# SAML21_Breakout.net
KiCad netlist of a schematic drawn in EAGLE
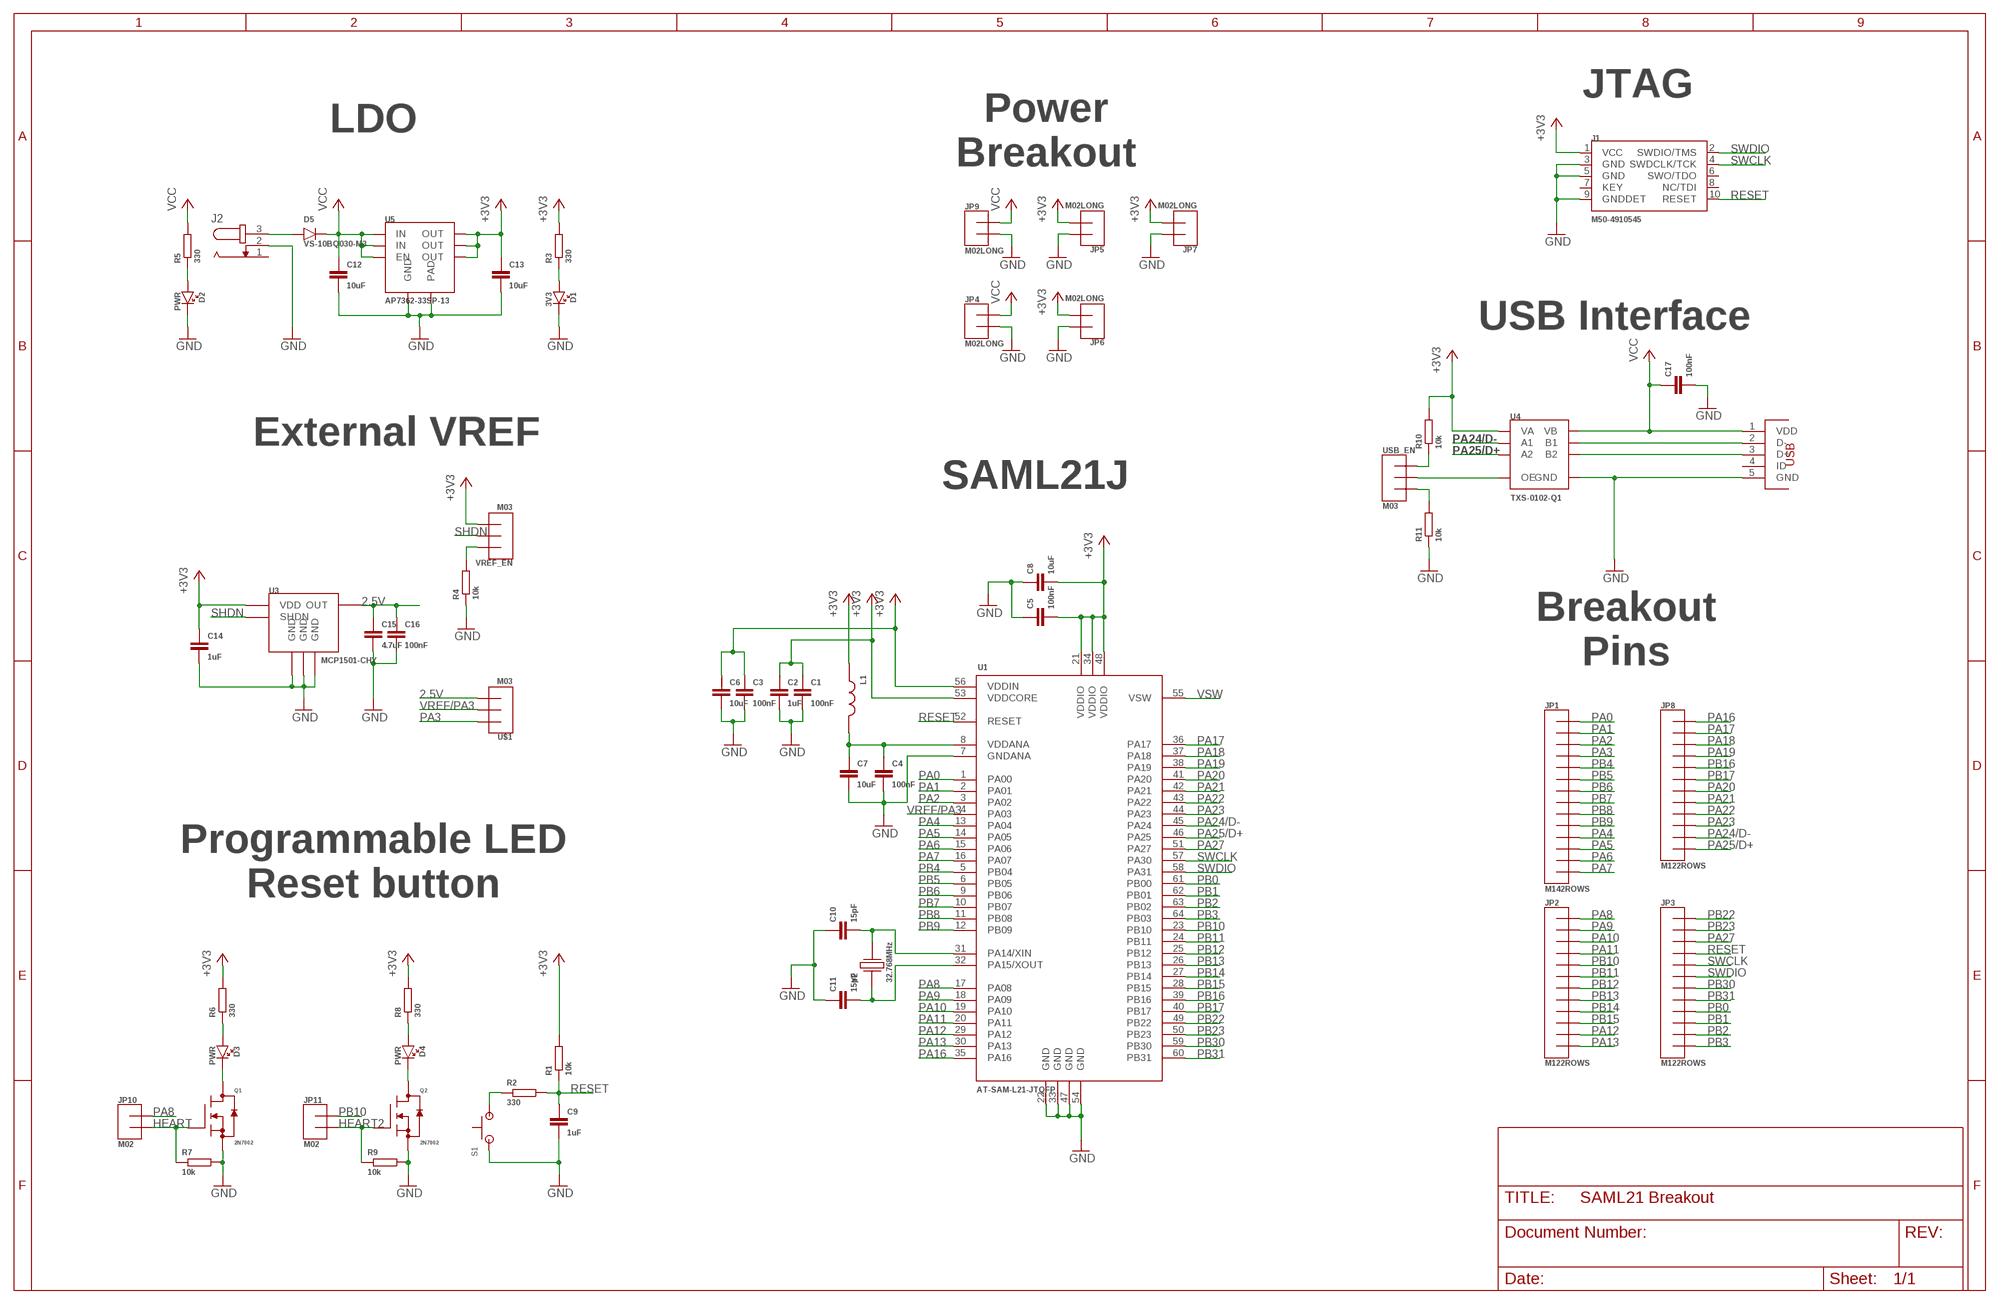
[diagram p0: schematic, sheet 1]

(export (version "E")
  (design (tool "Eeschema 10.0.6"))
  (components
    (comp (ref "C1")
      (value "100nF")
      (footprint "eagle-import:CAP-0603")
      (libsource (lib "eagle-import") (part "CAP0603"))
    )
    (comp (ref "C2")
      (value "1uF")
      (footprint "eagle-import:CAP-0603")
      (libsource (lib "eagle-import") (part "CAP0603"))
    )
    (comp (ref "C3")
      (value "100nF")
      (footprint "eagle-import:CAP-0603")
      (libsource (lib "eagle-import") (part "CAP0603"))
    )
    (comp (ref "C4")
      (value "100nF")
      (footprint "eagle-import:CAP-0603")
      (libsource (lib "eagle-import") (part "CAP0603"))
    )
    (comp (ref "C5")
      (value "100nF")
      (footprint "eagle-import:CAP-0603")
      (libsource (lib "eagle-import") (part "CAP0603"))
    )
    (comp (ref "C6")
      (value "10uF")
      (footprint "eagle-import:CAP-0603")
      (libsource (lib "eagle-import") (part "CAP0603"))
    )
    (comp (ref "C7")
      (value "10uF")
      (footprint "eagle-import:CAP-0603")
      (libsource (lib "eagle-import") (part "CAP0603"))
    )
    (comp (ref "C8")
      (value "10uF")
      (footprint "eagle-import:CAP-0603")
      (libsource (lib "eagle-import") (part "CAP0603"))
    )
    (comp (ref "C9")
      (value "1uF")
      (footprint "eagle-import:CAP-0603")
      (libsource (lib "eagle-import") (part "CAP0603"))
    )
    (comp (ref "C10")
      (value "15pF")
      (footprint "eagle-import:CAP-0603")
      (libsource (lib "eagle-import") (part "CAP0603"))
    )
    (comp (ref "C11")
      (value "15pF")
      (footprint "eagle-import:CAP-0603")
      (libsource (lib "eagle-import") (part "CAP0603"))
    )
    (comp (ref "C12")
      (value "10uF")
      (footprint "eagle-import:CAP-0603")
      (libsource (lib "eagle-import") (part "CAP0603"))
    )
    (comp (ref "C13")
      (value "10uF")
      (footprint "eagle-import:CAP-0603")
      (libsource (lib "eagle-import") (part "CAP0603"))
    )
    (comp (ref "C14")
      (value "1uF")
      (footprint "eagle-import:CAP-0603")
      (libsource (lib "eagle-import") (part "CAP0603"))
    )
    (comp (ref "C15")
      (value "4.7uF")
      (footprint "eagle-import:CAP-0603")
      (libsource (lib "eagle-import") (part "CAP0603"))
    )
    (comp (ref "C16")
      (value "100nF")
      (footprint "eagle-import:CAP-0603")
      (libsource (lib "eagle-import") (part "CAP0603"))
    )
    (comp (ref "C17")
      (value "100nF")
      (footprint "eagle-import:CAP-0603")
      (libsource (lib "eagle-import") (part "CAP0603"))
    )
    (comp (ref "D1")
      (value "3V3")
      (footprint "eagle-import:LED-1206")
      (libsource (lib "eagle-import") (part "LED1206"))
    )
    (comp (ref "D2")
      (value "PWR")
      (footprint "eagle-import:LED-1206")
      (libsource (lib "eagle-import") (part "LED1206"))
    )
    (comp (ref "D3")
      (value "PWR")
      (footprint "eagle-import:LED-1206")
      (libsource (lib "eagle-import") (part "LED1206"))
    )
    (comp (ref "D4")
      (value "PWR")
      (footprint "eagle-import:LED-1206")
      (libsource (lib "eagle-import") (part "LED1206"))
    )
    (comp (ref "D5")
      (value "VS-10BQ030-M3")
      (footprint "eagle-import:DO-214AA")
      (libsource (lib "eagle-import") (part "VS-10BQ030-M3"))
    )
    (comp (ref "J1")
      (value "M50-4910545")
      (footprint "eagle-import:M50-4910545")
      (libsource (lib "eagle-import") (part "M50-4910545"))
    )
    (comp (ref "J2")
      (value "JACK-PLUG0")
      (footprint "eagle-import:SPC4077")
      (libsource (lib "eagle-import") (part "JACK-PLUG0"))
    )
    (comp (ref "JP1")
      (value "M142ROWS")
      (footprint "eagle-import:2X07")
      (libsource (lib "eagle-import") (part "M142ROWS"))
    )
    (comp (ref "JP2")
      (value "M122ROWS")
      (footprint "eagle-import:2X06")
      (libsource (lib "eagle-import") (part "M122ROWS"))
    )
    (comp (ref "JP3")
      (value "M122ROWS")
      (footprint "eagle-import:2X06")
      (libsource (lib "eagle-import") (part "M122ROWS"))
    )
    (comp (ref "JP4")
      (value "M02LONG")
      (footprint "eagle-import:1X02-LONG")
      (libsource (lib "eagle-import") (part "M02LONG"))
    )
    (comp (ref "JP5")
      (value "M02LONG")
      (footprint "eagle-import:1X02-LONG")
      (libsource (lib "eagle-import") (part "M02LONG"))
    )
    (comp (ref "JP6")
      (value "M02LONG")
      (footprint "eagle-import:1X02-LONG")
      (libsource (lib "eagle-import") (part "M02LONG"))
    )
    (comp (ref "JP7")
      (value "M02LONG")
      (footprint "eagle-import:1X02-LONG")
      (libsource (lib "eagle-import") (part "M02LONG"))
    )
    (comp (ref "JP8")
      (value "M122ROWS")
      (footprint "eagle-import:2X06")
      (libsource (lib "eagle-import") (part "M122ROWS"))
    )
    (comp (ref "JP9")
      (value "M02LONG")
      (footprint "eagle-import:1X02-LONG")
      (libsource (lib "eagle-import") (part "M02LONG"))
    )
    (comp (ref "JP10")
      (value "M02")
      (footprint "eagle-import:1X02")
      (libsource (lib "eagle-import") (part "M02"))
    )
    (comp (ref "JP11")
      (value "M02")
      (footprint "eagle-import:1X02")
      (libsource (lib "eagle-import") (part "M02"))
    )
    (comp (ref "L1")
      (value "INDUCTOR0603")
      (footprint "eagle-import:IND-0603")
      (libsource (lib "eagle-import") (part "INDUCTOR0603"))
    )
    (comp (ref "Q1")
      (value "2N7002")
      (footprint "eagle-import:SOT-23-3")
      (libsource (lib "eagle-import") (part "2N7002"))
    )
    (comp (ref "Q2")
      (value "2N7002")
      (footprint "eagle-import:SOT-23-3")
      (libsource (lib "eagle-import") (part "2N7002"))
    )
    (comp (ref "R1")
      (value "10k")
      (footprint "eagle-import:RES-0805")
      (libsource (lib "eagle-import") (part "RESISTOR0805"))
    )
    (comp (ref "R2")
      (value "330")
      (footprint "eagle-import:RES-0805")
      (libsource (lib "eagle-import") (part "RESISTOR0805"))
    )
    (comp (ref "R3")
      (value "330")
      (footprint "eagle-import:RES-0805")
      (libsource (lib "eagle-import") (part "RESISTOR0805"))
    )
    (comp (ref "R4")
      (value "10k")
      (footprint "eagle-import:RES-0805")
      (libsource (lib "eagle-import") (part "RESISTOR0805"))
    )
    (comp (ref "R5")
      (value "330")
      (footprint "eagle-import:RES-0805")
      (libsource (lib "eagle-import") (part "RESISTOR0805"))
    )
    (comp (ref "R6")
      (value "330")
      (footprint "eagle-import:RES-0805")
      (libsource (lib "eagle-import") (part "RESISTOR0805"))
    )
    (comp (ref "R7")
      (value "10k")
      (footprint "eagle-import:RES-0805")
      (libsource (lib "eagle-import") (part "RESISTOR0805"))
    )
    (comp (ref "R8")
      (value "330")
      (footprint "eagle-import:RES-0805")
      (libsource (lib "eagle-import") (part "RESISTOR0805"))
    )
    (comp (ref "R9")
      (value "10k")
      (footprint "eagle-import:RES-0805")
      (libsource (lib "eagle-import") (part "RESISTOR0805"))
    )
    (comp (ref "R10")
      (value "10k")
      (footprint "eagle-import:RES-0805")
      (libsource (lib "eagle-import") (part "RESISTOR0805"))
    )
    (comp (ref "R11")
      (value "10k")
      (footprint "eagle-import:RES-0805")
      (libsource (lib "eagle-import") (part "RESISTOR0805"))
    )
    (comp (ref "S1")
      (value "SKHMQME010")
      (footprint "eagle-import:SKHMQME010")
      (libsource (lib "eagle-import") (part "SKHMQME010"))
    )
    (comp (ref "U$1")
      (value "M03")
      (footprint "eagle-import:1X03")
      (libsource (lib "eagle-import") (part "M03"))
    )
    (comp (ref "U$6")
      (value "MOLEX_USBMICRO")
      (footprint "eagle-import:MOLEX_47346-001")
      (libsource (lib "eagle-import") (part "MOLEX_USBMICRO"))
    )
    (comp (ref "U1")
      (value "AT-SAM-L21-JTQFP")
      (footprint "eagle-import:TQFP-64")
      (libsource (lib "eagle-import") (part "AT-SAM-L21-JTQFP"))
    )
    (comp (ref "U3")
      (value "MCP1501-CHY")
      (footprint "eagle-import:SOT-23-6")
      (libsource (lib "eagle-import") (part "MCP1501-CHY"))
    )
    (comp (ref "U4")
      (value "TXS-0102-Q1")
      (footprint "eagle-import:VSSOP-8")
      (libsource (lib "eagle-import") (part "TXS-0102-Q1"))
    )
    (comp (ref "U5")
      (value "AP7362-33SP-13")
      (footprint "eagle-import:SO-8EP")
      (libsource (lib "eagle-import") (part "AP7362-33SP-13"))
    )
    (comp (ref "USB_EN")
      (value "M03")
      (footprint "eagle-import:1X03")
      (libsource (lib "eagle-import") (part "M03"))
    )
    (comp (ref "VREF_EN")
      (value "M03")
      (footprint "eagle-import:1X03")
      (libsource (lib "eagle-import") (part "M03"))
    )
    (comp (ref "Y2")
      (value "32.768MHz")
      (footprint "eagle-import:CFPX-217")
      (libsource (lib "eagle-import") (part "LFXTAL054236-R"))
    )
  )
  (nets
    (net (code "1") (name "+3V3") (class "Default")
      (node (ref "C1") (pin "1") (pinfunction "1_1") (pintype "passive"))
      (node (ref "C13") (pin "1") (pinfunction "1_1") (pintype "passive"))
      (node (ref "C14") (pin "1") (pinfunction "1_1") (pintype "passive"))
      (node (ref "C2") (pin "1") (pinfunction "1_1") (pintype "passive"))
      (node (ref "C3") (pin "1") (pinfunction "1_1") (pintype "passive"))
      (node (ref "C5") (pin "2") (pinfunction "2_2") (pintype "passive"))
      (node (ref "C6") (pin "1") (pinfunction "1_1") (pintype "passive"))
      (node (ref "C8") (pin "2") (pinfunction "2_2") (pintype "passive"))
      (node (ref "J1") (pin "1") (pinfunction "VCC_1") (pintype "bidirectional"))
      (node (ref "JP5") (pin "2") (pinfunction "2_2") (pintype "bidirectional"))
      (node (ref "JP6") (pin "2") (pinfunction "2_2") (pintype "bidirectional"))
      (node (ref "JP7") (pin "2") (pinfunction "2_2") (pintype "bidirectional"))
      (node (ref "L1") (pin "1") (pinfunction "1_1") (pintype "passive"))
      (node (ref "R1") (pin "2") (pinfunction "2_2") (pintype "passive"))
      (node (ref "R10") (pin "2") (pinfunction "2_2") (pintype "passive"))
      (node (ref "R3") (pin "2") (pinfunction "2_2") (pintype "passive"))
      (node (ref "R6") (pin "2") (pinfunction "2_2") (pintype "passive"))
      (node (ref "R8") (pin "2") (pinfunction "2_2") (pintype "passive"))
      (node (ref "U1") (pin "21") (pinfunction "VDDIO_21") (pintype "power_in"))
      (node (ref "U1") (pin "34") (pinfunction "VDDIO_34") (pintype "power_in"))
      (node (ref "U1") (pin "48") (pinfunction "VDDIO_48") (pintype "power_in"))
      (node (ref "U1") (pin "53") (pinfunction "VDDCORE_53") (pintype "output"))
      (node (ref "U1") (pin "56") (pinfunction "VDDIN_56") (pintype "power_in"))
      (node (ref "U3") (pin "6") (pinfunction "VDD_6") (pintype "bidirectional"))
      (node (ref "U4") (pin "3") (pinfunction "VA_3") (pintype "bidirectional"))
      (node (ref "U5") (pin "5") (pinfunction "OUT_5") (pintype "bidirectional"))
      (node (ref "U5") (pin "6") (pinfunction "OUT_6") (pintype "bidirectional"))
      (node (ref "U5") (pin "7") (pinfunction "OUT_7") (pintype "bidirectional"))
      (node (ref "VREF_EN") (pin "3") (pinfunction "3_3") (pintype "bidirectional"))
    )
    (net (code "2") (name "/2.5V") (class "Default")
      (node (ref "C15") (pin "1") (pinfunction "1_1") (pintype "passive"))
      (node (ref "C16") (pin "1") (pinfunction "1_1") (pintype "passive"))
      (node (ref "U$1") (pin "3") (pinfunction "3_3") (pintype "bidirectional"))
      (node (ref "U3") (pin "1") (pinfunction "OUT_1") (pintype "bidirectional"))
    )
    (net (code "3") (name "/HEART") (class "Default")
      (node (ref "JP10") (pin "2") (pinfunction "2_2") (pintype "bidirectional"))
      (node (ref "Q1") (pin "D") (pinfunction "D_D") (pintype "bidirectional"))
      (node (ref "R7") (pin "1") (pinfunction "1_1") (pintype "passive"))
    )
    (net (code "4") (name "/HEART2") (class "Default")
      (node (ref "JP11") (pin "2") (pinfunction "2_2") (pintype "bidirectional"))
      (node (ref "Q2") (pin "D") (pinfunction "D_D") (pintype "bidirectional"))
      (node (ref "R9") (pin "1") (pinfunction "1_1") (pintype "passive"))
    )
    (net (code "5") (name "/PA0") (class "Default")
      (node (ref "JP1") (pin "1") (pinfunction "1_1") (pintype "bidirectional"))
      (node (ref "U1") (pin "1") (pinfunction "PA00_1") (pintype "bidirectional"))
    )
    (net (code "6") (name "/PA1") (class "Default")
      (node (ref "JP1") (pin "2") (pinfunction "2_2") (pintype "bidirectional"))
      (node (ref "U1") (pin "2") (pinfunction "PA01_2") (pintype "bidirectional"))
    )
    (net (code "7") (name "/PA2") (class "Default")
      (node (ref "JP1") (pin "3") (pinfunction "3_3") (pintype "bidirectional"))
      (node (ref "U1") (pin "3") (pinfunction "PA02_3") (pintype "bidirectional"))
    )
    (net (code "8") (name "/PA3") (class "Default")
      (node (ref "JP1") (pin "4") (pinfunction "4_4") (pintype "bidirectional"))
      (node (ref "U$1") (pin "1") (pinfunction "1_1") (pintype "bidirectional"))
    )
    (net (code "9") (name "/PA4") (class "Default")
      (node (ref "JP1") (pin "11") (pinfunction "11_11") (pintype "bidirectional"))
      (node (ref "U1") (pin "13") (pinfunction "PA04_13") (pintype "bidirectional"))
    )
    (net (code "10") (name "/PA5") (class "Default")
      (node (ref "JP1") (pin "12") (pinfunction "12_12") (pintype "bidirectional"))
      (node (ref "U1") (pin "14") (pinfunction "PA05_14") (pintype "bidirectional"))
    )
    (net (code "11") (name "/PA6") (class "Default")
      (node (ref "JP1") (pin "13") (pinfunction "13_13") (pintype "bidirectional"))
      (node (ref "U1") (pin "15") (pinfunction "PA06_15") (pintype "bidirectional"))
    )
    (net (code "12") (name "/PA7") (class "Default")
      (node (ref "JP1") (pin "14") (pinfunction "14_14") (pintype "bidirectional"))
      (node (ref "U1") (pin "16") (pinfunction "PA07_16") (pintype "bidirectional"))
    )
    (net (code "13") (name "/PA8") (class "Default")
      (node (ref "JP10") (pin "1") (pinfunction "1_1") (pintype "bidirectional"))
      (node (ref "JP2") (pin "1") (pinfunction "1_1") (pintype "bidirectional"))
      (node (ref "U1") (pin "17") (pinfunction "PA08_17") (pintype "bidirectional"))
    )
    (net (code "14") (name "/PA9") (class "Default")
      (node (ref "JP2") (pin "2") (pinfunction "2_2") (pintype "bidirectional"))
      (node (ref "U1") (pin "18") (pinfunction "PA09_18") (pintype "bidirectional"))
    )
    (net (code "15") (name "/PA10") (class "Default")
      (node (ref "JP2") (pin "3") (pinfunction "3_3") (pintype "bidirectional"))
      (node (ref "U1") (pin "19") (pinfunction "PA10_19") (pintype "bidirectional"))
    )
    (net (code "16") (name "/PA11") (class "Default")
      (node (ref "JP2") (pin "4") (pinfunction "4_4") (pintype "bidirectional"))
      (node (ref "U1") (pin "20") (pinfunction "PA11_20") (pintype "bidirectional"))
    )
    (net (code "17") (name "/PA12") (class "Default")
      (node (ref "JP2") (pin "11") (pinfunction "11_11") (pintype "bidirectional"))
      (node (ref "U1") (pin "29") (pinfunction "PA12_29") (pintype "bidirectional"))
    )
    (net (code "18") (name "/PA13") (class "Default")
      (node (ref "JP2") (pin "12") (pinfunction "12_12") (pintype "bidirectional"))
      (node (ref "U1") (pin "30") (pinfunction "PA13_30") (pintype "bidirectional"))
    )
    (net (code "19") (name "/PA16") (class "Default")
      (node (ref "JP8") (pin "1") (pinfunction "1_1") (pintype "bidirectional"))
      (node (ref "U1") (pin "35") (pinfunction "PA16_35") (pintype "bidirectional"))
    )
    (net (code "20") (name "/PA17") (class "Default")
      (node (ref "JP8") (pin "2") (pinfunction "2_2") (pintype "bidirectional"))
      (node (ref "U1") (pin "36") (pinfunction "PA17_36") (pintype "bidirectional"))
    )
    (net (code "21") (name "/PA18") (class "Default")
      (node (ref "JP8") (pin "3") (pinfunction "3_3") (pintype "bidirectional"))
      (node (ref "U1") (pin "37") (pinfunction "PA18_37") (pintype "bidirectional"))
    )
    (net (code "22") (name "/PA19") (class "Default")
      (node (ref "JP8") (pin "4") (pinfunction "4_4") (pintype "bidirectional"))
      (node (ref "U1") (pin "38") (pinfunction "PA19_38") (pintype "bidirectional"))
    )
    (net (code "23") (name "/PA20") (class "Default")
      (node (ref "JP8") (pin "7") (pinfunction "7_7") (pintype "bidirectional"))
      (node (ref "U1") (pin "41") (pinfunction "PA20_41") (pintype "bidirectional"))
    )
    (net (code "24") (name "/PA21") (class "Default")
      (node (ref "JP8") (pin "8") (pinfunction "8_8") (pintype "bidirectional"))
      (node (ref "U1") (pin "42") (pinfunction "PA21_42") (pintype "bidirectional"))
    )
    (net (code "25") (name "/PA22") (class "Default")
      (node (ref "JP8") (pin "9") (pinfunction "9_9") (pintype "bidirectional"))
      (node (ref "U1") (pin "43") (pinfunction "PA22_43") (pintype "bidirectional"))
    )
    (net (code "26") (name "/PA23") (class "Default")
      (node (ref "JP8") (pin "10") (pinfunction "10_10") (pintype "bidirectional"))
      (node (ref "U1") (pin "44") (pinfunction "PA23_44") (pintype "bidirectional"))
    )
    (net (code "27") (name "/PA24{slash}D-") (class "Default")
      (node (ref "JP8") (pin "11") (pinfunction "11_11") (pintype "bidirectional"))
      (node (ref "U1") (pin "45") (pinfunction "PA24_45") (pintype "bidirectional"))
      (node (ref "U4") (pin "5") (pinfunction "A1_5") (pintype "bidirectional"))
    )
    (net (code "28") (name "/PA25{slash}D+") (class "Default")
      (node (ref "JP8") (pin "12") (pinfunction "12_12") (pintype "bidirectional"))
      (node (ref "U1") (pin "46") (pinfunction "PA25_46") (pintype "bidirectional"))
      (node (ref "U4") (pin "4") (pinfunction "A2_4") (pintype "bidirectional"))
    )
    (net (code "29") (name "/PA27") (class "Default")
      (node (ref "JP3") (pin "3") (pinfunction "3_3") (pintype "bidirectional"))
      (node (ref "U1") (pin "51") (pinfunction "PA27_51") (pintype "bidirectional"))
    )
    (net (code "30") (name "/PB0") (class "Default")
      (node (ref "JP3") (pin "9") (pinfunction "9_9") (pintype "bidirectional"))
      (node (ref "U1") (pin "61") (pinfunction "PB00_61") (pintype "bidirectional"))
    )
    (net (code "31") (name "/PB1") (class "Default")
      (node (ref "JP3") (pin "10") (pinfunction "10_10") (pintype "bidirectional"))
      (node (ref "U1") (pin "62") (pinfunction "PB01_62") (pintype "bidirectional"))
    )
    (net (code "32") (name "/PB2") (class "Default")
      (node (ref "JP3") (pin "11") (pinfunction "11_11") (pintype "bidirectional"))
      (node (ref "U1") (pin "63") (pinfunction "PB02_63") (pintype "bidirectional"))
    )
    (net (code "33") (name "/PB3") (class "Default")
      (node (ref "JP3") (pin "12") (pinfunction "12_12") (pintype "bidirectional"))
      (node (ref "U1") (pin "64") (pinfunction "PB03_64") (pintype "bidirectional"))
    )
    (net (code "34") (name "/PB4") (class "Default")
      (node (ref "JP1") (pin "5") (pinfunction "5_5") (pintype "bidirectional"))
      (node (ref "U1") (pin "5") (pinfunction "PB04_5") (pintype "bidirectional"))
    )
    (net (code "35") (name "/PB5") (class "Default")
      (node (ref "JP1") (pin "6") (pinfunction "6_6") (pintype "bidirectional"))
      (node (ref "U1") (pin "6") (pinfunction "PB05_6") (pintype "bidirectional"))
    )
    (net (code "36") (name "/PB6") (class "Default")
      (node (ref "JP1") (pin "7") (pinfunction "7_7") (pintype "bidirectional"))
      (node (ref "U1") (pin "9") (pinfunction "PB06_9") (pintype "bidirectional"))
    )
    (net (code "37") (name "/PB7") (class "Default")
      (node (ref "JP1") (pin "8") (pinfunction "8_8") (pintype "bidirectional"))
      (node (ref "U1") (pin "10") (pinfunction "PB07_10") (pintype "bidirectional"))
    )
    (net (code "38") (name "/PB8") (class "Default")
      (node (ref "JP1") (pin "9") (pinfunction "9_9") (pintype "bidirectional"))
      (node (ref "U1") (pin "11") (pinfunction "PB08_11") (pintype "bidirectional"))
    )
    (net (code "39") (name "/PB9") (class "Default")
      (node (ref "JP1") (pin "10") (pinfunction "10_10") (pintype "bidirectional"))
      (node (ref "U1") (pin "12") (pinfunction "PB09_12") (pintype "bidirectional"))
    )
    (net (code "40") (name "/PB10") (class "Default")
      (node (ref "JP11") (pin "1") (pinfunction "1_1") (pintype "bidirectional"))
      (node (ref "JP2") (pin "5") (pinfunction "5_5") (pintype "bidirectional"))
      (node (ref "U1") (pin "23") (pinfunction "PB10_23") (pintype "bidirectional"))
    )
    (net (code "41") (name "/PB11") (class "Default")
      (node (ref "JP2") (pin "6") (pinfunction "6_6") (pintype "bidirectional"))
      (node (ref "U1") (pin "24") (pinfunction "PB11_24") (pintype "bidirectional"))
    )
    (net (code "42") (name "/PB12") (class "Default")
      (node (ref "JP2") (pin "7") (pinfunction "7_7") (pintype "bidirectional"))
      (node (ref "U1") (pin "25") (pinfunction "PB12_25") (pintype "bidirectional"))
    )
    (net (code "43") (name "/PB13") (class "Default")
      (node (ref "JP2") (pin "8") (pinfunction "8_8") (pintype "bidirectional"))
      (node (ref "U1") (pin "26") (pinfunction "PB13_26") (pintype "bidirectional"))
    )
    (net (code "44") (name "/PB14") (class "Default")
      (node (ref "JP2") (pin "9") (pinfunction "9_9") (pintype "bidirectional"))
      (node (ref "U1") (pin "27") (pinfunction "PB14_27") (pintype "bidirectional"))
    )
    (net (code "45") (name "/PB15") (class "Default")
      (node (ref "JP2") (pin "10") (pinfunction "10_10") (pintype "bidirectional"))
      (node (ref "U1") (pin "28") (pinfunction "PB15_28") (pintype "bidirectional"))
    )
    (net (code "46") (name "/PB16") (class "Default")
      (node (ref "JP8") (pin "5") (pinfunction "5_5") (pintype "bidirectional"))
      (node (ref "U1") (pin "39") (pinfunction "PB16_39") (pintype "bidirectional"))
    )
    (net (code "47") (name "/PB17") (class "Default")
      (node (ref "JP8") (pin "6") (pinfunction "6_6") (pintype "bidirectional"))
      (node (ref "U1") (pin "40") (pinfunction "PB17_40") (pintype "bidirectional"))
    )
    (net (code "48") (name "/PB22") (class "Default")
      (node (ref "JP3") (pin "1") (pinfunction "1_1") (pintype "bidirectional"))
      (node (ref "U1") (pin "49") (pinfunction "PB22_49") (pintype "bidirectional"))
    )
    (net (code "49") (name "/PB23") (class "Default")
      (node (ref "JP3") (pin "2") (pinfunction "2_2") (pintype "bidirectional"))
      (node (ref "U1") (pin "50") (pinfunction "PB23_50") (pintype "bidirectional"))
    )
    (net (code "50") (name "/PB30") (class "Default")
      (node (ref "JP3") (pin "7") (pinfunction "7_7") (pintype "bidirectional"))
      (node (ref "U1") (pin "59") (pinfunction "PB30_59") (pintype "bidirectional"))
    )
    (net (code "51") (name "/PB31") (class "Default")
      (node (ref "JP3") (pin "8") (pinfunction "8_8") (pintype "bidirectional"))
      (node (ref "U1") (pin "60") (pinfunction "PB31_60") (pintype "bidirectional"))
    )
    (net (code "52") (name "/RESET") (class "Default")
      (node (ref "C9") (pin "1") (pinfunction "1_1") (pintype "passive"))
      (node (ref "J1") (pin "10") (pinfunction "RESET_10") (pintype "bidirectional"))
      (node (ref "JP3") (pin "4") (pinfunction "4_4") (pintype "bidirectional"))
      (node (ref "R1") (pin "1") (pinfunction "1_1") (pintype "passive"))
      (node (ref "R2") (pin "2") (pinfunction "2_2") (pintype "passive"))
      (node (ref "U1") (pin "52") (pinfunction "RESET_52") (pintype "bidirectional"))
    )
    (net (code "53") (name "/SHDN") (class "Default")
      (node (ref "U3") (pin "4") (pinfunction "SHDN_4") (pintype "bidirectional"))
      (node (ref "VREF_EN") (pin "2") (pinfunction "2_2") (pintype "bidirectional"))
    )
    (net (code "54") (name "/SWCLK") (class "Default")
      (node (ref "J1") (pin "4") (pinfunction "SWDCLK/TCK_4") (pintype "bidirectional"))
      (node (ref "JP3") (pin "5") (pinfunction "5_5") (pintype "bidirectional"))
      (node (ref "U1") (pin "57") (pinfunction "PA30_57") (pintype "bidirectional"))
    )
    (net (code "55") (name "/SWDIO") (class "Default")
      (node (ref "J1") (pin "2") (pinfunction "SWDIO/TMS_2") (pintype "bidirectional"))
      (node (ref "JP3") (pin "6") (pinfunction "6_6") (pintype "bidirectional"))
      (node (ref "U1") (pin "58") (pinfunction "PA31_58") (pintype "bidirectional"))
    )
    (net (code "56") (name "/VREF{slash}PA3") (class "Default")
      (node (ref "U$1") (pin "2") (pinfunction "2_2") (pintype "bidirectional"))
      (node (ref "U1") (pin "4") (pinfunction "PA03_4") (pintype "bidirectional"))
    )
    (net (code "57") (name "/VSW") (class "Default")
      (node (ref "U1") (pin "55") (pinfunction "VSW_55") (pintype "bidirectional"))
    )
    (net (code "58") (name "GND") (class "Default")
      (node (ref "C1") (pin "2") (pinfunction "2_2") (pintype "passive"))
      (node (ref "C10") (pin "1") (pinfunction "1_1") (pintype "passive"))
      (node (ref "C11") (pin "1") (pinfunction "1_1") (pintype "passive"))
      (node (ref "C12") (pin "2") (pinfunction "2_2") (pintype "passive"))
      (node (ref "C13") (pin "2") (pinfunction "2_2") (pintype "passive"))
      (node (ref "C14") (pin "2") (pinfunction "2_2") (pintype "passive"))
      (node (ref "C15") (pin "2") (pinfunction "2_2") (pintype "passive"))
      (node (ref "C16") (pin "2") (pinfunction "2_2") (pintype "passive"))
      (node (ref "C17") (pin "2") (pinfunction "2_2") (pintype "passive"))
      (node (ref "C2") (pin "2") (pinfunction "2_2") (pintype "passive"))
      (node (ref "C3") (pin "2") (pinfunction "2_2") (pintype "passive"))
      (node (ref "C4") (pin "2") (pinfunction "2_2") (pintype "passive"))
      (node (ref "C5") (pin "1") (pinfunction "1_1") (pintype "passive"))
      (node (ref "C6") (pin "2") (pinfunction "2_2") (pintype "passive"))
      (node (ref "C7") (pin "2") (pinfunction "2_2") (pintype "passive"))
      (node (ref "C8") (pin "1") (pinfunction "1_1") (pintype "passive"))
      (node (ref "C9") (pin "2") (pinfunction "2_2") (pintype "passive"))
      (node (ref "D1") (pin "C") (pinfunction "C_C") (pintype "bidirectional"))
      (node (ref "D2") (pin "C") (pinfunction "C_C") (pintype "bidirectional"))
      (node (ref "J1") (pin "3") (pinfunction "GND_3") (pintype "bidirectional"))
      (node (ref "J1") (pin "5") (pinfunction "GND_5") (pintype "bidirectional"))
      (node (ref "J1") (pin "9") (pinfunction "GNDDET_9") (pintype "bidirectional"))
      (node (ref "J2") (pin "2") (pinfunction "2_2") (pintype "passive"))
      (node (ref "JP4") (pin "2") (pinfunction "2_2") (pintype "bidirectional"))
      (node (ref "JP5") (pin "1") (pinfunction "1_1") (pintype "bidirectional"))
      (node (ref "JP6") (pin "1") (pinfunction "1_1") (pintype "bidirectional"))
      (node (ref "JP7") (pin "1") (pinfunction "1_1") (pintype "bidirectional"))
      (node (ref "JP9") (pin "2") (pinfunction "2_2") (pintype "bidirectional"))
      (node (ref "Q1") (pin "S") (pinfunction "S_S") (pintype "bidirectional"))
      (node (ref "Q2") (pin "S") (pinfunction "S_S") (pintype "bidirectional"))
      (node (ref "R11") (pin "1") (pinfunction "1_1") (pintype "passive"))
      (node (ref "R4") (pin "1") (pinfunction "1_1") (pintype "passive"))
      (node (ref "R7") (pin "2") (pinfunction "2_2") (pintype "passive"))
      (node (ref "R9") (pin "2") (pinfunction "2_2") (pintype "passive"))
      (node (ref "S1") (pin "1") (pinfunction "1_1") (pintype "bidirectional"))
      (node (ref "U$6") (pin "5") (pinfunction "GND_5") (pintype "bidirectional"))
      (node (ref "U1") (pin "22") (pinfunction "GND_22") (pintype "power_in"))
      (node (ref "U1") (pin "33") (pinfunction "GND_33") (pintype "power_in"))
      (node (ref "U1") (pin "47") (pinfunction "GND_47") (pintype "power_in"))
      (node (ref "U1") (pin "54") (pinfunction "GND_54") (pintype "power_in"))
      (node (ref "U1") (pin "7") (pinfunction "GNDANA_7") (pintype "power_in"))
      (node (ref "U3") (pin "2") (pinfunction "GND_2") (pintype "bidirectional"))
      (node (ref "U3") (pin "3") (pinfunction "GND_3") (pintype "bidirectional"))
      (node (ref "U3") (pin "5") (pinfunction "GND_5") (pintype "bidirectional"))
      (node (ref "U4") (pin "2") (pinfunction "GND_2") (pintype "bidirectional"))
      (node (ref "U5") (pin "1") (pinfunction "GND_1") (pintype "bidirectional"))
      (node (ref "U5") (pin "PAD") (pinfunction "PAD_PAD") (pintype "bidirectional"))
    )
    (net (code "59") (name "Net-(D1-PadA)") (class "Default")
      (node (ref "D1") (pin "A") (pinfunction "A_A") (pintype "bidirectional"))
      (node (ref "R3") (pin "1") (pinfunction "1_1") (pintype "passive"))
    )
    (net (code "60") (name "Net-(D2-PadA)") (class "Default")
      (node (ref "D2") (pin "A") (pinfunction "A_A") (pintype "bidirectional"))
      (node (ref "R5") (pin "1") (pinfunction "1_1") (pintype "passive"))
    )
    (net (code "61") (name "Net-(D3-PadA)") (class "Default")
      (node (ref "D3") (pin "A") (pinfunction "A_A") (pintype "bidirectional"))
      (node (ref "R6") (pin "1") (pinfunction "1_1") (pintype "passive"))
    )
    (net (code "62") (name "Net-(D3-PadC)") (class "Default")
      (node (ref "D3") (pin "C") (pinfunction "C_C") (pintype "bidirectional"))
      (node (ref "Q1") (pin "G") (pinfunction "G_G") (pintype "bidirectional"))
    )
    (net (code "63") (name "Net-(D4-PadA)") (class "Default")
      (node (ref "D4") (pin "A") (pinfunction "A_A") (pintype "bidirectional"))
      (node (ref "R8") (pin "1") (pinfunction "1_1") (pintype "passive"))
    )
    (net (code "64") (name "Net-(D4-PadC)") (class "Default")
      (node (ref "D4") (pin "C") (pinfunction "C_C") (pintype "bidirectional"))
      (node (ref "Q2") (pin "G") (pinfunction "G_G") (pintype "bidirectional"))
    )
    (net (code "65") (name "Net-(D5-PadA)") (class "Default")
      (node (ref "D5") (pin "A") (pinfunction "A_A") (pintype "bidirectional"))
      (node (ref "J2") (pin "3") (pinfunction "3_3") (pintype "passive"))
    )
    (net (code "66") (name "Net-(R4-Pad2)") (class "Default")
      (node (ref "R4") (pin "2") (pinfunction "2_2") (pintype "passive"))
      (node (ref "VREF_EN") (pin "1") (pinfunction "1_1") (pintype "bidirectional"))
    )
    (net (code "67") (name "Net-(R10-Pad1)") (class "Default")
      (node (ref "R10") (pin "1") (pinfunction "1_1") (pintype "passive"))
      (node (ref "USB_EN") (pin "1") (pinfunction "1_1") (pintype "bidirectional"))
    )
    (net (code "68") (name "Net-(R11-Pad2)") (class "Default")
      (node (ref "R11") (pin "2") (pinfunction "2_2") (pintype "passive"))
      (node (ref "USB_EN") (pin "3") (pinfunction "3_3") (pintype "bidirectional"))
    )
    (net (code "69") (name "Net-(S1-2)") (class "Default")
      (node (ref "R2") (pin "1") (pinfunction "1_1") (pintype "passive"))
      (node (ref "S1") (pin "3") (pinfunction "2_3") (pintype "bidirectional"))
    )
    (net (code "70") (name "Net-(U$6-D+)") (class "Default")
      (node (ref "U$6") (pin "3") (pinfunction "D+_3") (pintype "bidirectional"))
      (node (ref "U4") (pin "1") (pinfunction "B2_1") (pintype "bidirectional"))
    )
    (net (code "71") (name "Net-(U$6-D-)") (class "Default")
      (node (ref "U$6") (pin "2") (pinfunction "D-_2") (pintype "bidirectional"))
      (node (ref "U4") (pin "8") (pinfunction "B1_8") (pintype "bidirectional"))
    )
    (net (code "72") (name "Net-(U1-PA14{slash}XIN)") (class "Default")
      (node (ref "C10") (pin "2") (pinfunction "2_2") (pintype "passive"))
      (node (ref "U1") (pin "31") (pinfunction "PA14/XIN_31") (pintype "bidirectional"))
      (node (ref "Y2") (pin "2") (pinfunction "2_2") (pintype "bidirectional"))
    )
    (net (code "73") (name "Net-(U1-PA15{slash}XOUT)") (class "Default")
      (node (ref "C11") (pin "2") (pinfunction "2_2") (pintype "passive"))
      (node (ref "U1") (pin "32") (pinfunction "PA15/XOUT_32") (pintype "bidirectional"))
      (node (ref "Y2") (pin "1") (pinfunction "1_1") (pintype "bidirectional"))
    )
    (net (code "74") (name "Net-(U1-VDDANA)") (class "Default")
      (node (ref "C4") (pin "1") (pinfunction "1_1") (pintype "passive"))
      (node (ref "C7") (pin "1") (pinfunction "1_1") (pintype "passive"))
      (node (ref "L1") (pin "2") (pinfunction "2_2") (pintype "passive"))
      (node (ref "U1") (pin "8") (pinfunction "VDDANA_8") (pintype "power_in"))
    )
    (net (code "75") (name "Net-(U4-OE)") (class "Default")
      (node (ref "U4") (pin "6") (pinfunction "OE_6") (pintype "bidirectional"))
      (node (ref "USB_EN") (pin "2") (pinfunction "2_2") (pintype "bidirectional"))
    )
    (net (code "76") (name "VCC") (class "Default")
      (node (ref "C12") (pin "1") (pinfunction "1_1") (pintype "passive"))
      (node (ref "C17") (pin "1") (pinfunction "1_1") (pintype "passive"))
      (node (ref "D5") (pin "C") (pinfunction "C_C") (pintype "bidirectional"))
      (node (ref "JP4") (pin "1") (pinfunction "1_1") (pintype "bidirectional"))
      (node (ref "JP9") (pin "1") (pinfunction "1_1") (pintype "bidirectional"))
      (node (ref "R5") (pin "2") (pinfunction "2_2") (pintype "passive"))
      (node (ref "U$6") (pin "1") (pinfunction "VDD_1") (pintype "bidirectional"))
      (node (ref "U4") (pin "7") (pinfunction "VB_7") (pintype "bidirectional"))
      (node (ref "U5") (pin "2") (pinfunction "EN_2") (pintype "bidirectional"))
      (node (ref "U5") (pin "3") (pinfunction "IN_3") (pintype "bidirectional"))
      (node (ref "U5") (pin "4") (pinfunction "IN_4") (pintype "bidirectional"))
    )
    (net (code "77") (name "unconnected-(J1-KEY-Pad7)") (class "Default")
      (node (ref "J1") (pin "7") (pinfunction "KEY_7") (pintype "bidirectional"))
    )
    (net (code "78") (name "unconnected-(J1-NC{slash}TDI-Pad8)") (class "Default")
      (node (ref "J1") (pin "8") (pinfunction "NC/TDI_8") (pintype "bidirectional"))
    )
    (net (code "79") (name "unconnected-(J1-SWO{slash}TDO-Pad6)") (class "Default")
      (node (ref "J1") (pin "6") (pinfunction "SWO/TDO_6") (pintype "bidirectional"))
    )
    (net (code "80") (name "unconnected-(J2-Pad1)") (class "Default")
      (node (ref "J2") (pin "1") (pinfunction "1_1") (pintype "passive"))
    )
    (net (code "81") (name "unconnected-(S1-3-Pad5)") (class "Default")
      (node (ref "S1") (pin "5") (pinfunction "3_5") (pintype "bidirectional"))
    )
    (net (code "82") (name "unconnected-(U$6-ID-Pad4)") (class "Default")
      (node (ref "U$6") (pin "4") (pinfunction "ID_4") (pintype "bidirectional"))
    )
    (net (code "83") (name "unconnected-(U5-NC-Pad8)") (class "Default")
      (node (ref "U5") (pin "8") (pinfunction "NC_8") (pintype "no_connect"))
    )
  )
)
